# Ultrafit_Breakout.net
KiCad netlist of a schematic drawn in Altium Designer
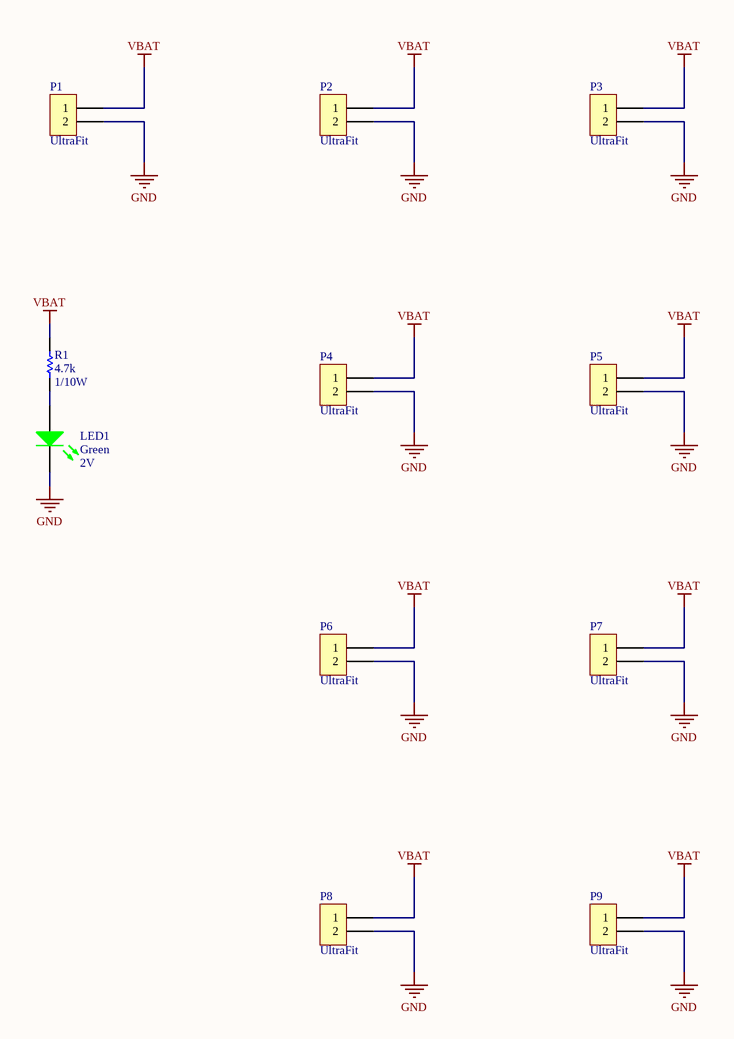
[diagram p0: Ultrafit Breakout.SchDoc]

(export (version "E")
  (design (tool "Eeschema 10.0.6"))
  (components
    (comp (ref "LED1")
      (value "LED GREEN CLEAR 2V 0603")
      (footprint "LED_0603")
      (description "Green 572nm LED Indication - Discrete 2V 0603 (1608 Metric)")
      (fields
        (field (name "MANUFACTURER") "Wurth Electronics Inc.")
        (field (name "MANUFACTURER PART NUMBER") "150060VS75000")
        (field (name "COLOR") "Green")
        (field (name "VOLTAGE - FORWARD (VF) (TYP)") "2V")
      )
      (libsource (lib "Schematic Diagrams") (part "LED GREEN CLEAR 2V 0603"))
    )
    (comp (ref "P1")
      (value "CONN 2POS ULTRA-FIT 0.138\"")
      (footprint "CONN, 2POS ULTRA-FIT")
      (description "2 Positions Header, Shrouded Connector 0.138\" (3.50mm) Through Hole Gold")
      (fields (field (name "VOLTAGE") "400V") (field (name "SERIES") "UltraFit"))
      (libsource (lib "Schematic Diagrams") (part "CONN 2POS ULTRA-FIT 0.138{dblquote}"))
    )
    (comp (ref "P2")
      (value "CONN 2POS ULTRA-FIT 0.138\"")
      (footprint "CONN, 2POS ULTRA-FIT")
      (description "2 Positions Header, Shrouded Connector 0.138\" (3.50mm) Through Hole Gold")
      (fields (field (name "VOLTAGE") "400V") (field (name "SERIES") "UltraFit"))
      (libsource (lib "Schematic Diagrams") (part "CONN 2POS ULTRA-FIT 0.138{dblquote}"))
    )
    (comp (ref "P3")
      (value "CONN 2POS ULTRA-FIT 0.138\"")
      (footprint "CONN, 2POS ULTRA-FIT")
      (description "2 Positions Header, Shrouded Connector 0.138\" (3.50mm) Through Hole Gold")
      (fields (field (name "VOLTAGE") "400V") (field (name "SERIES") "UltraFit"))
      (libsource (lib "Schematic Diagrams") (part "CONN 2POS ULTRA-FIT 0.138{dblquote}"))
    )
    (comp (ref "P4")
      (value "CONN 2POS ULTRA-FIT 0.138\"")
      (footprint "CONN, 2POS ULTRA-FIT")
      (description "2 Positions Header, Shrouded Connector 0.138\" (3.50mm) Through Hole Gold")
      (fields (field (name "VOLTAGE") "400V") (field (name "SERIES") "UltraFit"))
      (libsource (lib "Schematic Diagrams") (part "CONN 2POS ULTRA-FIT 0.138{dblquote}"))
    )
    (comp (ref "P5")
      (value "CONN 2POS ULTRA-FIT 0.138\"")
      (footprint "CONN, 2POS ULTRA-FIT")
      (description "2 Positions Header, Shrouded Connector 0.138\" (3.50mm) Through Hole Gold")
      (fields (field (name "VOLTAGE") "400V") (field (name "SERIES") "UltraFit"))
      (libsource (lib "Schematic Diagrams") (part "CONN 2POS ULTRA-FIT 0.138{dblquote}"))
    )
    (comp (ref "P6")
      (value "CONN 2POS ULTRA-FIT 0.138\"")
      (footprint "CONN, 2POS ULTRA-FIT")
      (description "2 Positions Header, Shrouded Connector 0.138\" (3.50mm) Through Hole Gold")
      (fields (field (name "VOLTAGE") "400V") (field (name "SERIES") "UltraFit"))
      (libsource (lib "Schematic Diagrams") (part "CONN 2POS ULTRA-FIT 0.138{dblquote}"))
    )
    (comp (ref "P7")
      (value "CONN 2POS ULTRA-FIT 0.138\"")
      (footprint "CONN, 2POS ULTRA-FIT")
      (description "2 Positions Header, Shrouded Connector 0.138\" (3.50mm) Through Hole Gold")
      (fields (field (name "VOLTAGE") "400V") (field (name "SERIES") "UltraFit"))
      (libsource (lib "Schematic Diagrams") (part "CONN 2POS ULTRA-FIT 0.138{dblquote}"))
    )
    (comp (ref "P8")
      (value "CONN 2POS ULTRA-FIT 0.138\"")
      (footprint "CONN, 2POS ULTRA-FIT")
      (description "2 Positions Header, Shrouded Connector 0.138\" (3.50mm) Through Hole Gold")
      (fields (field (name "VOLTAGE") "400V") (field (name "SERIES") "UltraFit"))
      (libsource (lib "Schematic Diagrams") (part "CONN 2POS ULTRA-FIT 0.138{dblquote}"))
    )
    (comp (ref "P9")
      (value "CONN 2POS ULTRA-FIT 0.138\"")
      (footprint "CONN, 2POS ULTRA-FIT")
      (description "2 Positions Header, Shrouded Connector 0.138\" (3.50mm) Through Hole Gold")
      (fields (field (name "VOLTAGE") "400V") (field (name "SERIES") "UltraFit"))
      (libsource (lib "Schematic Diagrams") (part "CONN 2POS ULTRA-FIT 0.138{dblquote}"))
    )
    (comp (ref "R1")
      (value "RES 4.7K OHM 1% 1/10W 0603")
      (footprint "RES, 0603")
      (description "4.7k Ohm ±1% 0.1W, 1/10W Chip Resistor 0603 (1608 Metric) Moisture Resistant Thick Film")
      (fields
        (field (name "TOLERANCE") "±1%")
        (field (name "RESISTANCE (OHMS)") "4.7k")
        (field (name "POWER (WATTS)") "1/10W")
      )
      (libsource (lib "Schematic Diagrams") (part "RES 4.7K OHM 1% 1/10W 0603"))
    )
  )
  (nets
    (net (code "1") (name "GND") (class "Default")
      (node (ref "LED1") (pin "2") (pinfunction "K_2") (pintype "passive"))
      (node (ref "P1") (pin "2") (pinfunction "2_2") (pintype "passive"))
      (node (ref "P2") (pin "2") (pinfunction "2_2") (pintype "passive"))
      (node (ref "P3") (pin "2") (pinfunction "2_2") (pintype "passive"))
      (node (ref "P4") (pin "2") (pinfunction "2_2") (pintype "passive"))
      (node (ref "P5") (pin "2") (pinfunction "2_2") (pintype "passive"))
      (node (ref "P6") (pin "2") (pinfunction "2_2") (pintype "passive"))
      (node (ref "P7") (pin "2") (pinfunction "2_2") (pintype "passive"))
      (node (ref "P8") (pin "2") (pinfunction "2_2") (pintype "passive"))
      (node (ref "P9") (pin "2") (pinfunction "2_2") (pintype "passive"))
    )
    (net (code "2") (name "Net-(LED1-A)") (class "Default")
      (node (ref "LED1") (pin "1") (pinfunction "A_1") (pintype "passive"))
      (node (ref "R1") (pin "2") (pinfunction "2_2") (pintype "passive"))
    )
    (net (code "3") (name "VBAT") (class "Default")
      (node (ref "P1") (pin "1") (pinfunction "1_1") (pintype "passive"))
      (node (ref "P2") (pin "1") (pinfunction "1_1") (pintype "passive"))
      (node (ref "P3") (pin "1") (pinfunction "1_1") (pintype "passive"))
      (node (ref "P4") (pin "1") (pinfunction "1_1") (pintype "passive"))
      (node (ref "P5") (pin "1") (pinfunction "1_1") (pintype "passive"))
      (node (ref "P6") (pin "1") (pinfunction "1_1") (pintype "passive"))
      (node (ref "P7") (pin "1") (pinfunction "1_1") (pintype "passive"))
      (node (ref "P8") (pin "1") (pinfunction "1_1") (pintype "passive"))
      (node (ref "P9") (pin "1") (pinfunction "1_1") (pintype "passive"))
      (node (ref "R1") (pin "1") (pinfunction "1_1") (pintype "passive"))
    )
  )
)
